# DDR3.net
KiCad netlist of a schematic drawn in Altium Designer
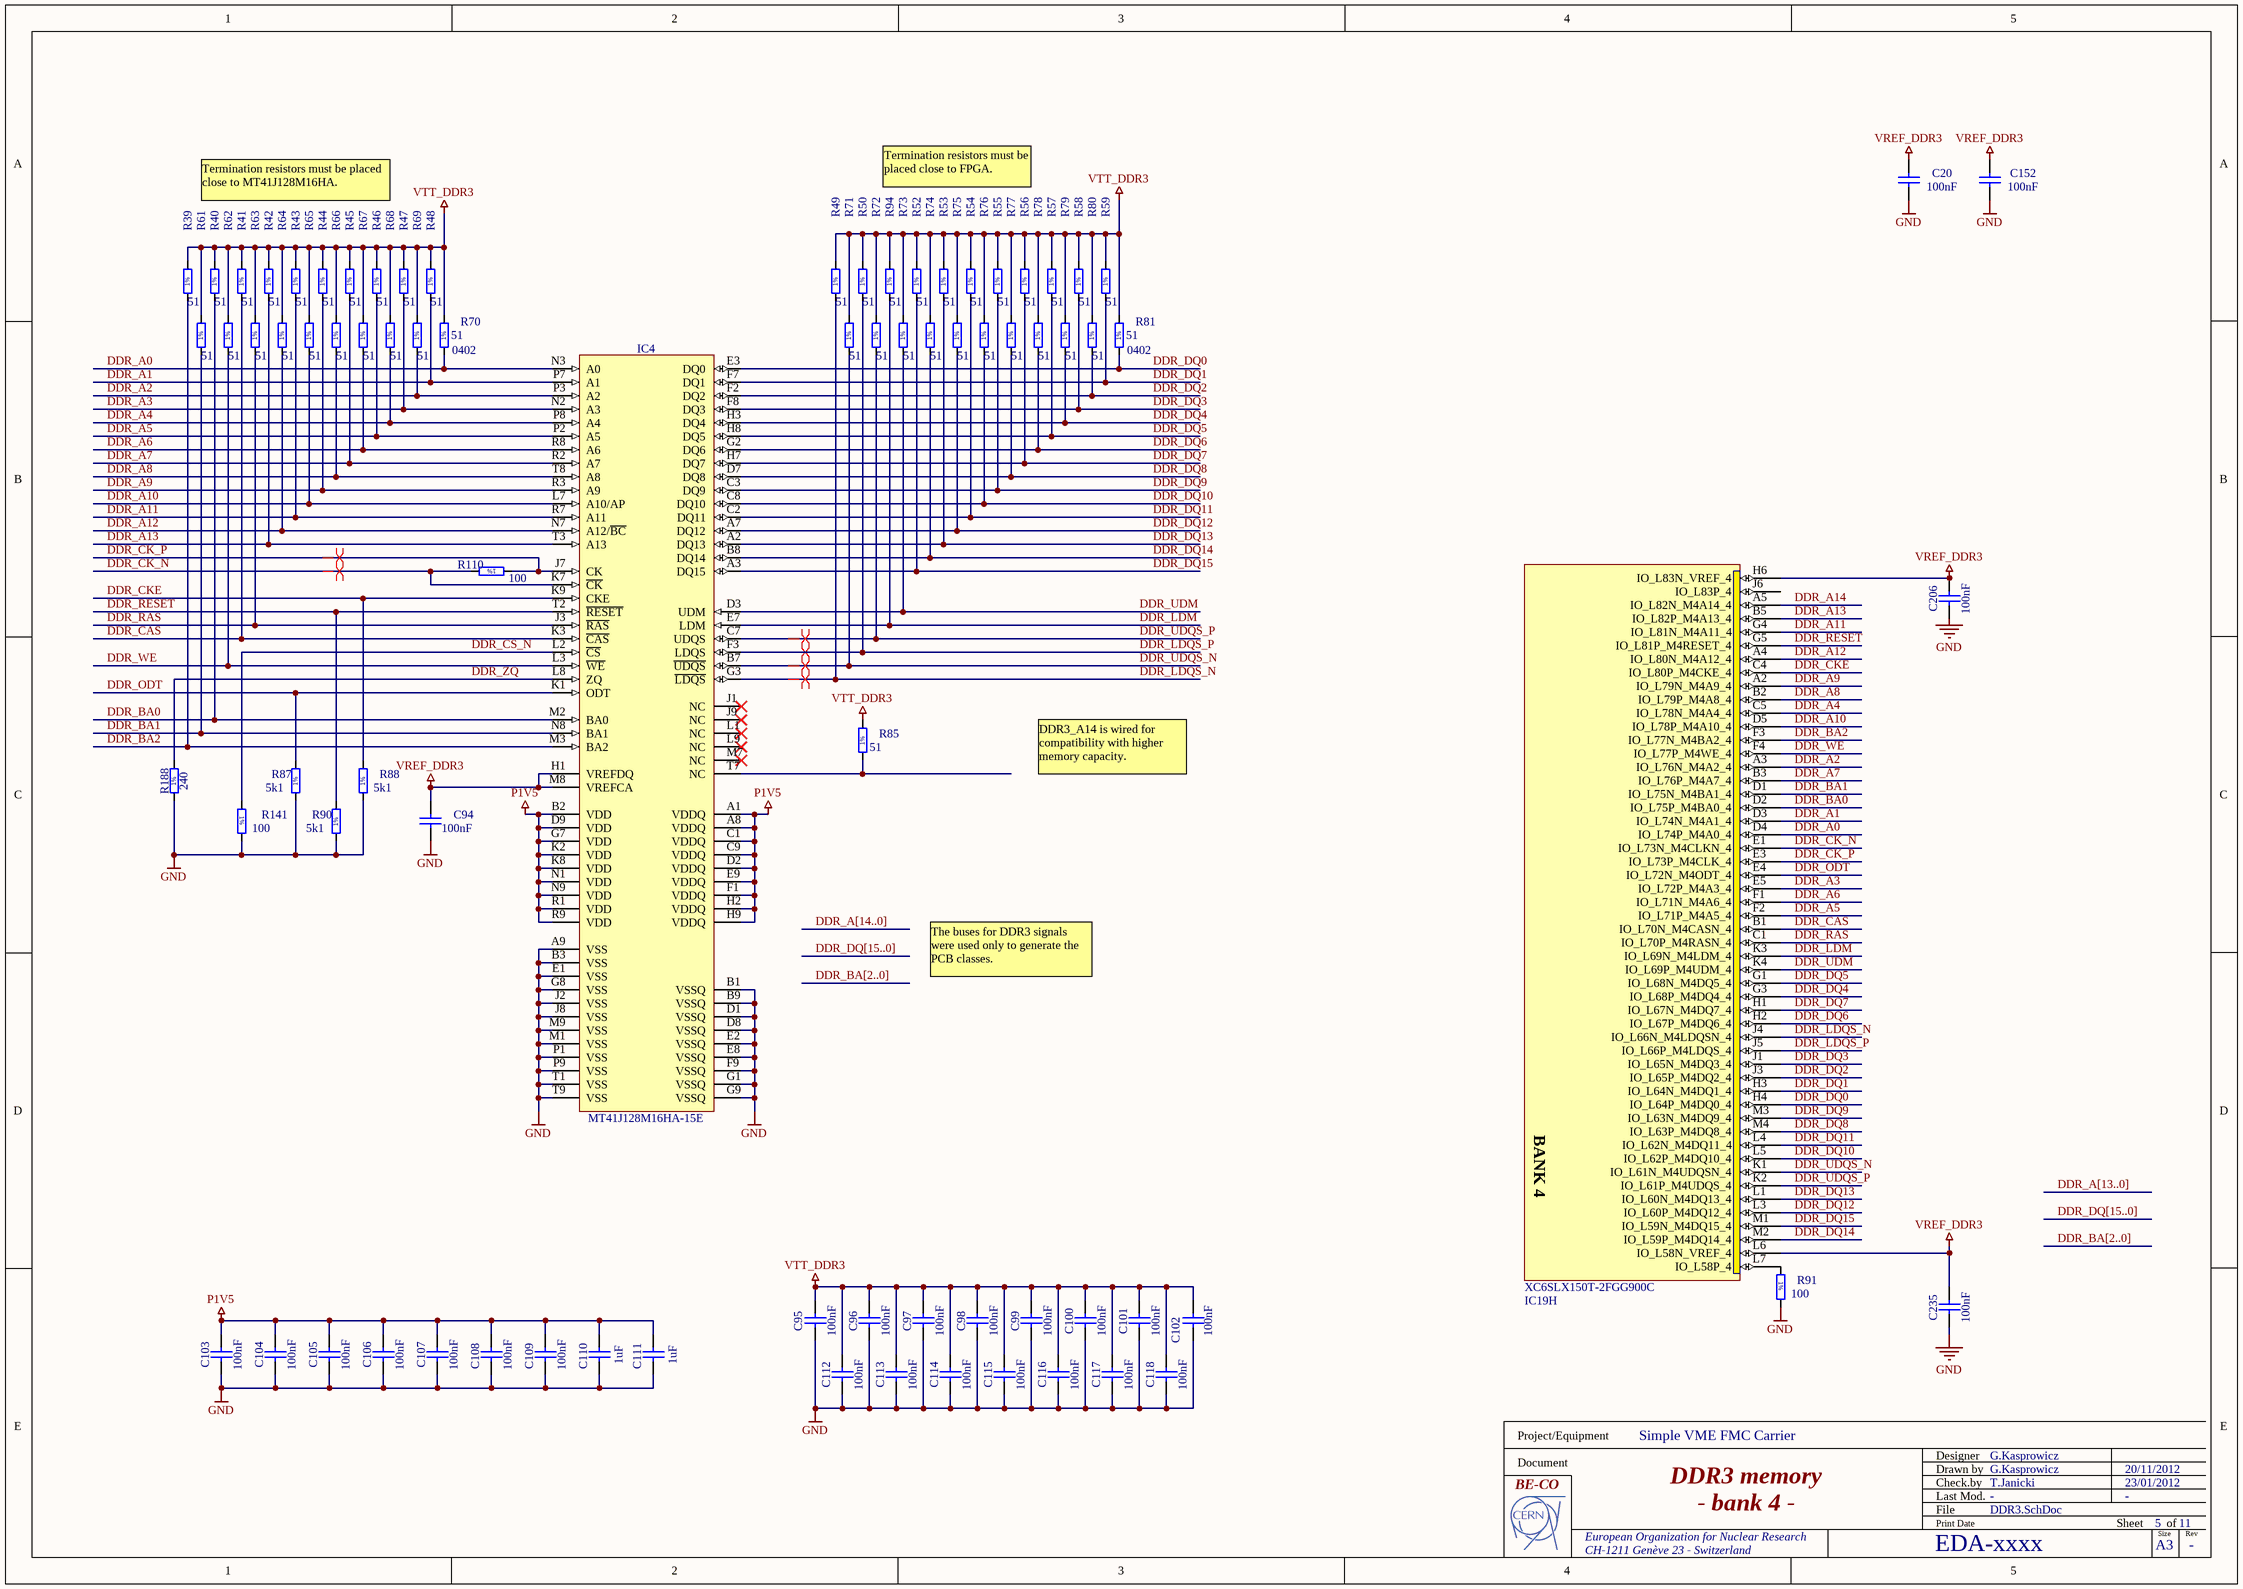
[diagram p0: DDR3.SchDoc]

(export (version "E")
  (design (tool "Eeschema 10.0.6"))
  (components
    (comp (ref "C20")
      (value "100nF")
      (footprint "CAPC1005X55N")
      (description "Non-polarised capacitor")
      (fields (field (name "PART NUMBER") "CC0402_100NF_16V_10%_X7R") (field (name "VOLTAGE") "16V"))
      (libsource (lib "Capacitors") (part "Capacitor - non polarized"))
    )
    (comp (ref "C94")
      (value "100nF")
      (footprint "CAPC1005X55N")
      (description "Non-polarised capacitor")
      (fields (field (name "PART NUMBER") "CC0402_100NF_16V_10%_X7R") (field (name "VOLTAGE") "16V"))
      (libsource (lib "Capacitors") (part "Capacitor - non polarized"))
    )
    (comp (ref "C95")
      (value "100nF")
      (footprint "CAPC1005X55N")
      (description "Non-polarised capacitor")
      (fields (field (name "PART NUMBER") "CC0402_100NF_16V_10%_X7R") (field (name "VOLTAGE") "16V"))
      (libsource (lib "Capacitors") (part "Capacitor - non polarized"))
    )
    (comp (ref "C96")
      (value "100nF")
      (footprint "CAPC1005X55N")
      (description "Non-polarised capacitor")
      (fields (field (name "PART NUMBER") "CC0402_100NF_16V_10%_X7R") (field (name "VOLTAGE") "16V"))
      (libsource (lib "Capacitors") (part "Capacitor - non polarized"))
    )
    (comp (ref "C97")
      (value "100nF")
      (footprint "CAPC1005X55N")
      (description "Non-polarised capacitor")
      (fields (field (name "PART NUMBER") "CC0402_100NF_16V_10%_X7R") (field (name "VOLTAGE") "16V"))
      (libsource (lib "Capacitors") (part "Capacitor - non polarized"))
    )
    (comp (ref "C98")
      (value "100nF")
      (footprint "CAPC1005X55N")
      (description "Non-polarised capacitor")
      (fields (field (name "PART NUMBER") "CC0402_100NF_16V_10%_X7R") (field (name "VOLTAGE") "16V"))
      (libsource (lib "Capacitors") (part "Capacitor - non polarized"))
    )
    (comp (ref "C99")
      (value "100nF")
      (footprint "CAPC1005X55N")
      (description "Non-polarised capacitor")
      (fields (field (name "PART NUMBER") "CC0402_100NF_16V_10%_X7R") (field (name "VOLTAGE") "16V"))
      (libsource (lib "Capacitors") (part "Capacitor - non polarized"))
    )
    (comp (ref "C100")
      (value "100nF")
      (footprint "CAPC1005X55N")
      (description "Non-polarised capacitor")
      (fields (field (name "PART NUMBER") "CC0402_100NF_16V_10%_X7R") (field (name "VOLTAGE") "16V"))
      (libsource (lib "Capacitors") (part "Capacitor - non polarized"))
    )
    (comp (ref "C101")
      (value "100nF")
      (footprint "CAPC1005X55N")
      (description "Non-polarised capacitor")
      (fields (field (name "PART NUMBER") "CC0402_100NF_16V_10%_X7R") (field (name "VOLTAGE") "16V"))
      (libsource (lib "Capacitors") (part "Capacitor - non polarized"))
    )
    (comp (ref "C102")
      (value "100nF")
      (footprint "CAPC1005X55N")
      (description "Non-polarised capacitor")
      (fields (field (name "PART NUMBER") "CC0402_100NF_16V_10%_X7R") (field (name "VOLTAGE") "16V"))
      (libsource (lib "Capacitors") (part "Capacitor - non polarized"))
    )
    (comp (ref "C103")
      (value "100nF")
      (footprint "CAPC1005X55N")
      (description "Non-polarised capacitor")
      (fields (field (name "PART NUMBER") "CC0402_100NF_16V_10%_X7R") (field (name "VOLTAGE") "16V"))
      (libsource (lib "Capacitors") (part "Capacitor - non polarized"))
    )
    (comp (ref "C104")
      (value "100nF")
      (footprint "CAPC1005X55N")
      (description "Non-polarised capacitor")
      (fields (field (name "PART NUMBER") "CC0402_100NF_16V_10%_X7R") (field (name "VOLTAGE") "16V"))
      (libsource (lib "Capacitors") (part "Capacitor - non polarized"))
    )
    (comp (ref "C105")
      (value "100nF")
      (footprint "CAPC1005X55N")
      (description "Non-polarised capacitor")
      (fields (field (name "PART NUMBER") "CC0402_100NF_16V_10%_X7R") (field (name "VOLTAGE") "16V"))
      (libsource (lib "Capacitors") (part "Capacitor - non polarized"))
    )
    (comp (ref "C106")
      (value "100nF")
      (footprint "CAPC1005X55N")
      (description "Non-polarised capacitor")
      (fields (field (name "PART NUMBER") "CC0402_100NF_16V_10%_X7R") (field (name "VOLTAGE") "16V"))
      (libsource (lib "Capacitors") (part "Capacitor - non polarized"))
    )
    (comp (ref "C107")
      (value "100nF")
      (footprint "CAPC1005X55N")
      (description "Non-polarised capacitor")
      (fields (field (name "PART NUMBER") "CC0402_100NF_16V_10%_X7R") (field (name "VOLTAGE") "16V"))
      (libsource (lib "Capacitors") (part "Capacitor - non polarized"))
    )
    (comp (ref "C108")
      (value "100nF")
      (footprint "CAPC1005X55N")
      (description "Non-polarised capacitor")
      (fields (field (name "PART NUMBER") "CC0402_100NF_16V_10%_X7R") (field (name "VOLTAGE") "16V"))
      (libsource (lib "Capacitors") (part "Capacitor - non polarized"))
    )
    (comp (ref "C109")
      (value "100nF")
      (footprint "CAPC1005X55N")
      (description "Non-polarised capacitor")
      (fields (field (name "PART NUMBER") "CC0402_100NF_16V_10%_X7R") (field (name "VOLTAGE") "16V"))
      (libsource (lib "Capacitors") (part "Capacitor - non polarized"))
    )
    (comp (ref "C110")
      (value "1uF")
      (footprint "CAPC1608X87N")
      (description "Non-polarised capacitor")
      (fields (field (name "PART NUMBER") "CC0603_1UF_16V_10%_X7R") (field (name "VOLTAGE") "16V"))
      (libsource (lib "Capacitors") (part "Capacitor - non polarized"))
    )
    (comp (ref "C111")
      (value "1uF")
      (footprint "CAPC1608X87N")
      (description "Non-polarised capacitor")
      (fields (field (name "PART NUMBER") "CC0603_1UF_16V_10%_X7R") (field (name "VOLTAGE") "16V"))
      (libsource (lib "Capacitors") (part "Capacitor - non polarized"))
    )
    (comp (ref "C112")
      (value "100nF")
      (footprint "CAPC1005X55N")
      (description "Non-polarised capacitor")
      (fields (field (name "PART NUMBER") "CC0402_100NF_16V_10%_X7R") (field (name "VOLTAGE") "16V"))
      (libsource (lib "Capacitors") (part "Capacitor - non polarized"))
    )
    (comp (ref "C113")
      (value "100nF")
      (footprint "CAPC1005X55N")
      (description "Non-polarised capacitor")
      (fields (field (name "PART NUMBER") "CC0402_100NF_16V_10%_X7R") (field (name "VOLTAGE") "16V"))
      (libsource (lib "Capacitors") (part "Capacitor - non polarized"))
    )
    (comp (ref "C114")
      (value "100nF")
      (footprint "CAPC1005X55N")
      (description "Non-polarised capacitor")
      (fields (field (name "PART NUMBER") "CC0402_100NF_16V_10%_X7R") (field (name "VOLTAGE") "16V"))
      (libsource (lib "Capacitors") (part "Capacitor - non polarized"))
    )
    (comp (ref "C115")
      (value "100nF")
      (footprint "CAPC1005X55N")
      (description "Non-polarised capacitor")
      (fields (field (name "PART NUMBER") "CC0402_100NF_16V_10%_X7R") (field (name "VOLTAGE") "16V"))
      (libsource (lib "Capacitors") (part "Capacitor - non polarized"))
    )
    (comp (ref "C116")
      (value "100nF")
      (footprint "CAPC1005X55N")
      (description "Non-polarised capacitor")
      (fields (field (name "PART NUMBER") "CC0402_100NF_16V_10%_X7R") (field (name "VOLTAGE") "16V"))
      (libsource (lib "Capacitors") (part "Capacitor - non polarized"))
    )
    (comp (ref "C117")
      (value "100nF")
      (footprint "CAPC1005X55N")
      (description "Non-polarised capacitor")
      (fields (field (name "PART NUMBER") "CC0402_100NF_16V_10%_X7R") (field (name "VOLTAGE") "16V"))
      (libsource (lib "Capacitors") (part "Capacitor - non polarized"))
    )
    (comp (ref "C118")
      (value "100nF")
      (footprint "CAPC1005X55N")
      (description "Non-polarised capacitor")
      (fields (field (name "PART NUMBER") "CC0402_100NF_16V_10%_X7R") (field (name "VOLTAGE") "16V"))
      (libsource (lib "Capacitors") (part "Capacitor - non polarized"))
    )
    (comp (ref "C152")
      (value "100nF")
      (footprint "CAPC1005X55N")
      (description "Non-polarised capacitor")
      (fields (field (name "PART NUMBER") "CC0402_100NF_16V_10%_X7R") (field (name "VOLTAGE") "16V"))
      (libsource (lib "Capacitors") (part "Capacitor - non polarized"))
    )
    (comp (ref "C206")
      (value "100nF")
      (footprint "CAPC1005X55N")
      (description "Non-polarised capacitor")
      (fields (field (name "PART NUMBER") "CC0402_100NF_16V_10%_X7R") (field (name "VOLTAGE") "16V"))
      (libsource (lib "Capacitors") (part "Capacitor - non polarized"))
    )
    (comp (ref "C235")
      (value "100nF")
      (footprint "CAPC1005X55N")
      (description "Non-polarised capacitor")
      (fields (field (name "PART NUMBER") "CC0402_100NF_16V_10%_X7R") (field (name "VOLTAGE") "16V"))
      (libsource (lib "Capacitors") (part "Capacitor - non polarized"))
    )
    (comp (ref "IC4")
      (value "MT41J128M16HA-15E")
      (footprint "BGA96C80P9X16_900X1400X120")
      (description "16 Meg x 16 x 8 Banks DDR3 SDRAM")
      (fields (field (name "MANUFACTURER") "MICRON TECHNOLOGY"))
      (libsource (lib "ICs And Semiconductors") (part "MT41J128M16HA"))
    )
    (comp (ref "IC19")
      (value "XC6SLX150T-2FGG900C")
      (footprint "BGA900C100P30X30_3100X3100X260")
      (description "SPARTAN-6, FPGA, 900-Ball BGA, Commercial Grade, Pb-Free")
      (fields (field (name "MANUFACTURER") "XILINX"))
      (libsource (lib "ICs And Semiconductors") (part "XC6SLX150T-2FGG900C"))
    )
    (comp (ref "R39")
      (value "51")
      (footprint "RESC1005X40N")
      (description "Resistor - 1%")
      (fields (field (name "PART NUMBER") "R0402_51R_1%_0.0625W_100PPM") (field (name "POWER") "0.0625W"))
      (libsource (lib "Resistors") (part "Resistor - 1%"))
    )
    (comp (ref "R40")
      (value "51")
      (footprint "RESC1005X40N")
      (description "Resistor - 1%")
      (fields (field (name "PART NUMBER") "R0402_51R_1%_0.0625W_100PPM") (field (name "POWER") "0.0625W"))
      (libsource (lib "Resistors") (part "Resistor - 1%"))
    )
    (comp (ref "R41")
      (value "51")
      (footprint "RESC1005X40N")
      (description "Resistor - 1%")
      (fields (field (name "PART NUMBER") "R0402_51R_1%_0.0625W_100PPM") (field (name "POWER") "0.0625W"))
      (libsource (lib "Resistors") (part "Resistor - 1%"))
    )
    (comp (ref "R42")
      (value "51")
      (footprint "RESC1005X40N")
      (description "Resistor - 1%")
      (fields (field (name "PART NUMBER") "R0402_51R_1%_0.0625W_100PPM") (field (name "POWER") "0.0625W"))
      (libsource (lib "Resistors") (part "Resistor - 1%"))
    )
    (comp (ref "R43")
      (value "51")
      (footprint "RESC1005X40N")
      (description "Resistor - 1%")
      (fields (field (name "PART NUMBER") "R0402_51R_1%_0.0625W_100PPM") (field (name "POWER") "0.0625W"))
      (libsource (lib "Resistors") (part "Resistor - 1%"))
    )
    (comp (ref "R44")
      (value "51")
      (footprint "RESC1005X40N")
      (description "Resistor - 1%")
      (fields (field (name "PART NUMBER") "R0402_51R_1%_0.0625W_100PPM") (field (name "POWER") "0.0625W"))
      (libsource (lib "Resistors") (part "Resistor - 1%"))
    )
    (comp (ref "R45")
      (value "51")
      (footprint "RESC1005X40N")
      (description "Resistor - 1%")
      (fields (field (name "PART NUMBER") "R0402_51R_1%_0.0625W_100PPM") (field (name "POWER") "0.0625W"))
      (libsource (lib "Resistors") (part "Resistor - 1%"))
    )
    (comp (ref "R46")
      (value "51")
      (footprint "RESC1005X40N")
      (description "Resistor - 1%")
      (fields (field (name "PART NUMBER") "R0402_51R_1%_0.0625W_100PPM") (field (name "POWER") "0.0625W"))
      (libsource (lib "Resistors") (part "Resistor - 1%"))
    )
    (comp (ref "R47")
      (value "51")
      (footprint "RESC1005X40N")
      (description "Resistor - 1%")
      (fields (field (name "PART NUMBER") "R0402_51R_1%_0.0625W_100PPM") (field (name "POWER") "0.0625W"))
      (libsource (lib "Resistors") (part "Resistor - 1%"))
    )
    (comp (ref "R48")
      (value "51")
      (footprint "RESC1005X40N")
      (description "Resistor - 1%")
      (fields (field (name "PART NUMBER") "R0402_51R_1%_0.0625W_100PPM") (field (name "POWER") "0.0625W"))
      (libsource (lib "Resistors") (part "Resistor - 1%"))
    )
    (comp (ref "R49")
      (value "51")
      (footprint "RESC1005X40N")
      (description "Resistor - 1%")
      (fields (field (name "PART NUMBER") "R0402_51R_1%_0.0625W_100PPM") (field (name "POWER") "0.0625W"))
      (libsource (lib "Resistors") (part "Resistor - 1%"))
    )
    (comp (ref "R50")
      (value "51")
      (footprint "RESC1005X40N")
      (description "Resistor - 1%")
      (fields (field (name "PART NUMBER") "R0402_51R_1%_0.0625W_100PPM") (field (name "POWER") "0.0625W"))
      (libsource (lib "Resistors") (part "Resistor - 1%"))
    )
    (comp (ref "R52")
      (value "51")
      (footprint "RESC1005X40N")
      (description "Resistor - 1%")
      (fields (field (name "PART NUMBER") "R0402_51R_1%_0.0625W_100PPM") (field (name "POWER") "0.0625W"))
      (libsource (lib "Resistors") (part "Resistor - 1%"))
    )
    (comp (ref "R53")
      (value "51")
      (footprint "RESC1005X40N")
      (description "Resistor - 1%")
      (fields (field (name "PART NUMBER") "R0402_51R_1%_0.0625W_100PPM") (field (name "POWER") "0.0625W"))
      (libsource (lib "Resistors") (part "Resistor - 1%"))
    )
    (comp (ref "R54")
      (value "51")
      (footprint "RESC1005X40N")
      (description "Resistor - 1%")
      (fields (field (name "PART NUMBER") "R0402_51R_1%_0.0625W_100PPM") (field (name "POWER") "0.0625W"))
      (libsource (lib "Resistors") (part "Resistor - 1%"))
    )
    (comp (ref "R55")
      (value "51")
      (footprint "RESC1005X40N")
      (description "Resistor - 1%")
      (fields (field (name "PART NUMBER") "R0402_51R_1%_0.0625W_100PPM") (field (name "POWER") "0.0625W"))
      (libsource (lib "Resistors") (part "Resistor - 1%"))
    )
    (comp (ref "R56")
      (value "51")
      (footprint "RESC1005X40N")
      (description "Resistor - 1%")
      (fields (field (name "PART NUMBER") "R0402_51R_1%_0.0625W_100PPM") (field (name "POWER") "0.0625W"))
      (libsource (lib "Resistors") (part "Resistor - 1%"))
    )
    (comp (ref "R57")
      (value "51")
      (footprint "RESC1005X40N")
      (description "Resistor - 1%")
      (fields (field (name "PART NUMBER") "R0402_51R_1%_0.0625W_100PPM") (field (name "POWER") "0.0625W"))
      (libsource (lib "Resistors") (part "Resistor - 1%"))
    )
    (comp (ref "R58")
      (value "51")
      (footprint "RESC1005X40N")
      (description "Resistor - 1%")
      (fields (field (name "PART NUMBER") "R0402_51R_1%_0.0625W_100PPM") (field (name "POWER") "0.0625W"))
      (libsource (lib "Resistors") (part "Resistor - 1%"))
    )
    (comp (ref "R59")
      (value "51")
      (footprint "RESC1005X40N")
      (description "Resistor - 1%")
      (fields (field (name "PART NUMBER") "R0402_51R_1%_0.0625W_100PPM") (field (name "POWER") "0.0625W"))
      (libsource (lib "Resistors") (part "Resistor - 1%"))
    )
    (comp (ref "R61")
      (value "51")
      (footprint "RESC1005X40N")
      (description "Resistor - 1%")
      (fields (field (name "PART NUMBER") "R0402_51R_1%_0.0625W_100PPM") (field (name "POWER") "0.0625W"))
      (libsource (lib "Resistors") (part "Resistor - 1%"))
    )
    (comp (ref "R62")
      (value "51")
      (footprint "RESC1005X40N")
      (description "Resistor - 1%")
      (fields (field (name "PART NUMBER") "R0402_51R_1%_0.0625W_100PPM") (field (name "POWER") "0.0625W"))
      (libsource (lib "Resistors") (part "Resistor - 1%"))
    )
    (comp (ref "R63")
      (value "51")
      (footprint "RESC1005X40N")
      (description "Resistor - 1%")
      (fields (field (name "PART NUMBER") "R0402_51R_1%_0.0625W_100PPM") (field (name "POWER") "0.0625W"))
      (libsource (lib "Resistors") (part "Resistor - 1%"))
    )
    (comp (ref "R64")
      (value "51")
      (footprint "RESC1005X40N")
      (description "Resistor - 1%")
      (fields (field (name "PART NUMBER") "R0402_51R_1%_0.0625W_100PPM") (field (name "POWER") "0.0625W"))
      (libsource (lib "Resistors") (part "Resistor - 1%"))
    )
    (comp (ref "R65")
      (value "51")
      (footprint "RESC1005X40N")
      (description "Resistor - 1%")
      (fields (field (name "PART NUMBER") "R0402_51R_1%_0.0625W_100PPM") (field (name "POWER") "0.0625W"))
      (libsource (lib "Resistors") (part "Resistor - 1%"))
    )
    (comp (ref "R66")
      (value "51")
      (footprint "RESC1005X40N")
      (description "Resistor - 1%")
      (fields (field (name "PART NUMBER") "R0402_51R_1%_0.0625W_100PPM") (field (name "POWER") "0.0625W"))
      (libsource (lib "Resistors") (part "Resistor - 1%"))
    )
    (comp (ref "R67")
      (value "51")
      (footprint "RESC1005X40N")
      (description "Resistor - 1%")
      (fields (field (name "PART NUMBER") "R0402_51R_1%_0.0625W_100PPM") (field (name "POWER") "0.0625W"))
      (libsource (lib "Resistors") (part "Resistor - 1%"))
    )
    (comp (ref "R68")
      (value "51")
      (footprint "RESC1005X40N")
      (description "Resistor - 1%")
      (fields (field (name "PART NUMBER") "R0402_51R_1%_0.0625W_100PPM") (field (name "POWER") "0.0625W"))
      (libsource (lib "Resistors") (part "Resistor - 1%"))
    )
    (comp (ref "R69")
      (value "51")
      (footprint "RESC1005X40N")
      (description "Resistor - 1%")
      (fields (field (name "PART NUMBER") "R0402_51R_1%_0.0625W_100PPM") (field (name "POWER") "0.0625W"))
      (libsource (lib "Resistors") (part "Resistor - 1%"))
    )
    (comp (ref "R70")
      (value "51")
      (footprint "RESC1005X40N")
      (description "Resistor - 1%")
      (fields
        (field (name "PART NUMBER") "R0402_51R_1%_0.0625W_100PPM")
        (field (name "POWER") "0.0625W")
        (field (name "CASE") "0402")
      )
      (libsource (lib "Resistors") (part "Resistor - 1%"))
    )
    (comp (ref "R71")
      (value "51")
      (footprint "RESC1005X40N")
      (description "Resistor - 1%")
      (fields (field (name "PART NUMBER") "R0402_51R_1%_0.0625W_100PPM") (field (name "POWER") "0.0625W"))
      (libsource (lib "Resistors") (part "Resistor - 1%"))
    )
    (comp (ref "R72")
      (value "51")
      (footprint "RESC1005X40N")
      (description "Resistor - 1%")
      (fields (field (name "PART NUMBER") "R0402_51R_1%_0.0625W_100PPM") (field (name "POWER") "0.0625W"))
      (libsource (lib "Resistors") (part "Resistor - 1%"))
    )
    (comp (ref "R73")
      (value "51")
      (footprint "RESC1005X40N")
      (description "Resistor - 1%")
      (fields (field (name "PART NUMBER") "R0402_51R_1%_0.0625W_100PPM") (field (name "POWER") "0.0625W"))
      (libsource (lib "Resistors") (part "Resistor - 1%"))
    )
    (comp (ref "R74")
      (value "51")
      (footprint "RESC1005X40N")
      (description "Resistor - 1%")
      (fields (field (name "PART NUMBER") "R0402_51R_1%_0.0625W_100PPM") (field (name "POWER") "0.0625W"))
      (libsource (lib "Resistors") (part "Resistor - 1%"))
    )
    (comp (ref "R75")
      (value "51")
      (footprint "RESC1005X40N")
      (description "Resistor - 1%")
      (fields (field (name "PART NUMBER") "R0402_51R_1%_0.0625W_100PPM") (field (name "POWER") "0.0625W"))
      (libsource (lib "Resistors") (part "Resistor - 1%"))
    )
    (comp (ref "R76")
      (value "51")
      (footprint "RESC1005X40N")
      (description "Resistor - 1%")
      (fields (field (name "PART NUMBER") "R0402_51R_1%_0.0625W_100PPM") (field (name "POWER") "0.0625W"))
      (libsource (lib "Resistors") (part "Resistor - 1%"))
    )
    (comp (ref "R77")
      (value "51")
      (footprint "RESC1005X40N")
      (description "Resistor - 1%")
      (fields (field (name "PART NUMBER") "R0402_51R_1%_0.0625W_100PPM") (field (name "POWER") "0.0625W"))
      (libsource (lib "Resistors") (part "Resistor - 1%"))
    )
    (comp (ref "R78")
      (value "51")
      (footprint "RESC1005X40N")
      (description "Resistor - 1%")
      (fields (field (name "PART NUMBER") "R0402_51R_1%_0.0625W_100PPM") (field (name "POWER") "0.0625W"))
      (libsource (lib "Resistors") (part "Resistor - 1%"))
    )
    (comp (ref "R79")
      (value "51")
      (footprint "RESC1005X40N")
      (description "Resistor - 1%")
      (fields (field (name "PART NUMBER") "R0402_51R_1%_0.0625W_100PPM") (field (name "POWER") "0.0625W"))
      (libsource (lib "Resistors") (part "Resistor - 1%"))
    )
    (comp (ref "R80")
      (value "51")
      (footprint "RESC1005X40N")
      (description "Resistor - 1%")
      (fields (field (name "PART NUMBER") "R0402_51R_1%_0.0625W_100PPM") (field (name "POWER") "0.0625W"))
      (libsource (lib "Resistors") (part "Resistor - 1%"))
    )
    (comp (ref "R81")
      (value "51")
      (footprint "RESC1005X40N")
      (description "Resistor - 1%")
      (fields
        (field (name "PART NUMBER") "R0402_51R_1%_0.0625W_100PPM")
        (field (name "POWER") "0.0625W")
        (field (name "CASE") "0402")
      )
      (libsource (lib "Resistors") (part "Resistor - 1%"))
    )
    (comp (ref "R85")
      (value "51")
      (footprint "RESC1005X40N")
      (description "Resistor - 1%")
      (fields (field (name "PART NUMBER") "R0402_51R_1%_0.0625W_100PPM") (field (name "POWER") "0.0625W"))
      (libsource (lib "Resistors") (part "Resistor - 1%"))
    )
    (comp (ref "R87")
      (value "5k1")
      (footprint "RESC1608X55N")
      (description "Resistor - 1%")
      (fields (field (name "PART NUMBER") "R0603_5K1_1%_0.1W_100PPM") (field (name "POWER") "0.1W"))
      (libsource (lib "Resistors") (part "Resistor - 1%"))
    )
    (comp (ref "R88")
      (value "5k1")
      (footprint "RESC1608X55N")
      (description "Resistor - 1%")
      (fields (field (name "PART NUMBER") "R0603_5K1_1%_0.1W_100PPM") (field (name "POWER") "0.1W"))
      (libsource (lib "Resistors") (part "Resistor - 1%"))
    )
    (comp (ref "R90")
      (value "5k1")
      (footprint "RESC1608X55N")
      (description "Resistor - 1%")
      (fields (field (name "PART NUMBER") "R0603_5K1_1%_0.1W_100PPM") (field (name "POWER") "0.1W"))
      (libsource (lib "Resistors") (part "Resistor - 1%"))
    )
    (comp (ref "R91")
      (value "100")
      (footprint "RESC1608X55N")
      (description "Resistor - 1%")
      (fields (field (name "PART NUMBER") "R0603_100R_1%_0.1W_100PPM") (field (name "POWER") "0.1W"))
      (libsource (lib "Resistors") (part "Resistor - 1%"))
    )
    (comp (ref "R94")
      (value "51")
      (footprint "RESC1005X40N")
      (description "Resistor - 1%")
      (fields (field (name "PART NUMBER") "R0402_51R_1%_0.0625W_100PPM") (field (name "POWER") "0.0625W"))
      (libsource (lib "Resistors") (part "Resistor - 1%"))
    )
    (comp (ref "R110")
      (value "100")
      (footprint "RESC1608X55N")
      (description "Resistor - 1%")
      (fields (field (name "PART NUMBER") "R0603_100R_1%_0.1W_100PPM") (field (name "POWER") "0.1W"))
      (libsource (lib "Resistors") (part "Resistor - 1%"))
    )
    (comp (ref "R141")
      (value "100")
      (footprint "RESC1608X55N")
      (description "Resistor - 1%")
      (fields (field (name "PART NUMBER") "R0603_100R_1%_0.1W_100PPM") (field (name "POWER") "0.1W"))
      (libsource (lib "Resistors") (part "Resistor - 1%"))
    )
    (comp (ref "R188")
      (value "240")
      (footprint "RESC1608X55N")
      (description "Resistor - 1%")
      (fields (field (name "PART NUMBER") "R0603_240R_1%_0.1W_100PPM") (field (name "POWER") "0.1W"))
      (libsource (lib "Resistors") (part "Resistor - 1%"))
    )
  )
  (nets
    (net (code "1") (name "/DDR_A0") (class "Default")
      (node (ref "IC19") (pin "D4") (pinfunction "IO_L74P_M4A0_4_D4") (pintype "bidirectional"))
      (node (ref "IC4") (pin "N3") (pinfunction "A0_N3") (pintype "input"))
      (node (ref "R70") (pin "1") (pinfunction "1_1") (pintype "passive"))
    )
    (net (code "2") (name "/DDR_A1") (class "Default")
      (node (ref "IC19") (pin "D3") (pinfunction "IO_L74N_M4A1_4_D3") (pintype "bidirectional"))
      (node (ref "IC4") (pin "P7") (pinfunction "A1_P7") (pintype "input"))
      (node (ref "R48") (pin "1") (pinfunction "1_1") (pintype "passive"))
    )
    (net (code "3") (name "/DDR_A2") (class "Default")
      (node (ref "IC19") (pin "A3") (pinfunction "IO_L76N_M4A2_4_A3") (pintype "bidirectional"))
      (node (ref "IC4") (pin "P3") (pinfunction "A2_P3") (pintype "input"))
      (node (ref "R69") (pin "1") (pinfunction "1_1") (pintype "passive"))
    )
    (net (code "4") (name "/DDR_A3") (class "Default")
      (node (ref "IC19") (pin "E5") (pinfunction "IO_L72P_M4A3_4_E5") (pintype "bidirectional"))
      (node (ref "IC4") (pin "N2") (pinfunction "A3_N2") (pintype "input"))
      (node (ref "R47") (pin "1") (pinfunction "1_1") (pintype "passive"))
    )
    (net (code "5") (name "/DDR_A4") (class "Default")
      (node (ref "IC19") (pin "C5") (pinfunction "IO_L78N_M4A4_4_C5") (pintype "bidirectional"))
      (node (ref "IC4") (pin "P8") (pinfunction "A4_P8") (pintype "input"))
      (node (ref "R68") (pin "1") (pinfunction "1_1") (pintype "passive"))
    )
    (net (code "6") (name "/DDR_A5") (class "Default")
      (node (ref "IC19") (pin "F2") (pinfunction "IO_L71P_M4A5_4_F2") (pintype "bidirectional"))
      (node (ref "IC4") (pin "P2") (pinfunction "A5_P2") (pintype "input"))
      (node (ref "R46") (pin "1") (pinfunction "1_1") (pintype "passive"))
    )
    (net (code "7") (name "/DDR_A6") (class "Default")
      (node (ref "IC19") (pin "F1") (pinfunction "IO_L71N_M4A6_4_F1") (pintype "bidirectional"))
      (node (ref "IC4") (pin "R8") (pinfunction "A6_R8") (pintype "input"))
      (node (ref "R67") (pin "1") (pinfunction "1_1") (pintype "passive"))
    )
    (net (code "8") (name "/DDR_A7") (class "Default")
      (node (ref "IC19") (pin "B3") (pinfunction "IO_L76P_M4A7_4_B3") (pintype "bidirectional"))
      (node (ref "IC4") (pin "R2") (pinfunction "A7_R2") (pintype "input"))
      (node (ref "R45") (pin "1") (pinfunction "1_1") (pintype "passive"))
    )
    (net (code "9") (name "/DDR_A8") (class "Default")
      (node (ref "IC19") (pin "B2") (pinfunction "IO_L79P_M4A8_4_B2") (pintype "bidirectional"))
      (node (ref "IC4") (pin "T8") (pinfunction "A8_T8") (pintype "input"))
      (node (ref "R66") (pin "1") (pinfunction "1_1") (pintype "passive"))
    )
    (net (code "10") (name "/DDR_A9") (class "Default")
      (node (ref "IC19") (pin "A2") (pinfunction "IO_L79N_M4A9_4_A2") (pintype "bidirectional"))
      (node (ref "IC4") (pin "R3") (pinfunction "A9_R3") (pintype "input"))
      (node (ref "R44") (pin "1") (pinfunction "1_1") (pintype "passive"))
    )
    (net (code "11") (name "/DDR_A10") (class "Default")
      (node (ref "IC19") (pin "D5") (pinfunction "IO_L78P_M4A10_4_D5") (pintype "bidirectional"))
      (node (ref "IC4") (pin "L7") (pinfunction "A10/AP_L7") (pintype "input"))
      (node (ref "R65") (pin "1") (pinfunction "1_1") (pintype "passive"))
    )
    (net (code "12") (name "/DDR_A11") (class "Default")
      (node (ref "IC19") (pin "G4") (pinfunction "IO_L81N_M4A11_4_G4") (pintype "bidirectional"))
      (node (ref "IC4") (pin "R7") (pinfunction "A11_R7") (pintype "input"))
      (node (ref "R43") (pin "1") (pinfunction "1_1") (pintype "passive"))
    )
    (net (code "13") (name "/DDR_A12") (class "Default")
      (node (ref "IC19") (pin "A4") (pinfunction "IO_L80N_M4A12_4_A4") (pintype "bidirectional"))
      (node (ref "IC4") (pin "N7") (pinfunction "A12/~{BC}_N7") (pintype "input"))
      (node (ref "R64") (pin "1") (pinfunction "1_1") (pintype "passive"))
    )
    (net (code "14") (name "/DDR_A13") (class "Default")
      (node (ref "IC19") (pin "B5") (pinfunction "IO_L82P_M4A13_4_B5") (pintype "bidirectional"))
      (node (ref "IC4") (pin "T3") (pinfunction "A13_T3") (pintype "input"))
      (node (ref "R42") (pin "1") (pinfunction "1_1") (pintype "passive"))
    )
    (net (code "15") (name "/DDR_A14") (class "Default")
      (node (ref "IC19") (pin "A5") (pinfunction "IO_L82N_M4A14_4_A5") (pintype "bidirectional"))
    )
    (net (code "18") (name "/DDR_BA0") (class "Default")
      (node (ref "IC19") (pin "D2") (pinfunction "IO_L75P_M4BA0_4_D2") (pintype "bidirectional"))
      (node (ref "IC4") (pin "M2") (pinfunction "BA0_M2") (pintype "input"))
      (node (ref "R40") (pin "1") (pinfunction "1_1") (pintype "passive"))
    )
    (net (code "19") (name "/DDR_BA1") (class "Default")
      (node (ref "IC19") (pin "D1") (pinfunction "IO_L75N_M4BA1_4_D1") (pintype "bidirectional"))
      (node (ref "IC4") (pin "N8") (pinfunction "BA1_N8") (pintype "input"))
      (node (ref "R61") (pin "1") (pinfunction "1_1") (pintype "passive"))
    )
    (net (code "20") (name "/DDR_BA2") (class "Default")
      (node (ref "IC19") (pin "F3") (pinfunction "IO_L77N_M4BA2_4_F3") (pintype "bidirectional"))
      (node (ref "IC4") (pin "M3") (pinfunction "BA2_M3") (pintype "input"))
      (node (ref "R39") (pin "1") (pinfunction "1_1") (pintype "passive"))
    )
    (net (code "22") (name "/DDR_CAS") (class "Default")
      (node (ref "IC19") (pin "B1") (pinfunction "IO_L70N_M4CASN_4_B1") (pintype "bidirectional"))
      (node (ref "IC4") (pin "K3") (pinfunction "CAS_K3") (pintype "input"))
      (node (ref "R41") (pin "1") (pinfunction "1_1") (pintype "passive"))
    )
    (net (code "23") (name "/DDR_CKE") (class "Default")
      (node (ref "IC19") (pin "C4") (pinfunction "IO_L80P_M4CKE_4_C4") (pintype "bidirectional"))
      (node (ref "IC4") (pin "K9") (pinfunction "CKE_K9") (pintype "input"))
      (node (ref "R88") (pin "2") (pinfunction "2_2") (pintype "passive"))
    )
    (net (code "24") (name "/DDR_CK_N") (class "Default")
      (node (ref "IC19") (pin "E1") (pinfunction "IO_L73N_M4CLKN_4_E1") (pintype "bidirectional"))
      (node (ref "IC4") (pin "K7") (pinfunction "CK_K7") (pintype "input"))
      (node (ref "R110") (pin "2") (pinfunction "2_2") (pintype "passive"))
    )
    (net (code "25") (name "/DDR_CK_P") (class "Default")
      (node (ref "IC19") (pin "E3") (pinfunction "IO_L73P_M4CLK_4_E3") (pintype "bidirectional"))
      (node (ref "IC4") (pin "J7") (pinfunction "CK_J7") (pintype "input"))
      (node (ref "R110") (pin "1") (pinfunction "1_1") (pintype "passive"))
    )
    (net (code "26") (name "/DDR_CS_N") (class "Default")
      (node (ref "IC4") (pin "L2") (pinfunction "CS_L2") (pintype "input"))
      (node (ref "R141") (pin "1") (pinfunction "1_1") (pintype "passive"))
    )
    (net (code "27") (name "/DDR_DQ0") (class "Default")
      (node (ref "IC19") (pin "H4") (pinfunction "IO_L64P_M4DQ0_4_H4") (pintype "bidirectional"))
      (node (ref "IC4") (pin "E3") (pinfunction "DQ0_E3") (pintype "bidirectional"))
      (node (ref "R81") (pin "1") (pinfunction "1_1") (pintype "passive"))
    )
    (net (code "28") (name "/DDR_DQ1") (class "Default")
      (node (ref "IC19") (pin "H3") (pinfunction "IO_L64N_M4DQ1_4_H3") (pintype "bidirectional"))
      (node (ref "IC4") (pin "F7") (pinfunction "DQ1_F7") (pintype "bidirectional"))
      (node (ref "R59") (pin "1") (pinfunction "1_1") (pintype "passive"))
    )
    (net (code "29") (name "/DDR_DQ2") (class "Default")
      (node (ref "IC19") (pin "J3") (pinfunction "IO_L65P_M4DQ2_4_J3") (pintype "bidirectional"))
      (node (ref "IC4") (pin "F2") (pinfunction "DQ2_F2") (pintype "bidirectional"))
      (node (ref "R80") (pin "1") (pinfunction "1_1") (pintype "passive"))
    )
    (net (code "30") (name "/DDR_DQ3") (class "Default")
      (node (ref "IC19") (pin "J1") (pinfunction "IO_L65N_M4DQ3_4_J1") (pintype "bidirectional"))
      (node (ref "IC4") (pin "F8") (pinfunction "DQ3_F8") (pintype "bidirectional"))
      (node (ref "R58") (pin "1") (pinfunction "1_1") (pintype "passive"))
    )
    (net (code "31") (name "/DDR_DQ4") (class "Default")
      (node (ref "IC19") (pin "G3") (pinfunction "IO_L68P_M4DQ4_4_G3") (pintype "bidirectional"))
      (node (ref "IC4") (pin "H3") (pinfunction "DQ4_H3") (pintype "bidirectional"))
      (node (ref "R79") (pin "1") (pinfunction "1_1") (pintype "passive"))
    )
    (net (code "32") (name "/DDR_DQ5") (class "Default")
      (node (ref "IC19") (pin "G1") (pinfunction "IO_L68N_M4DQ5_4_G1") (pintype "bidirectional"))
      (node (ref "IC4") (pin "H8") (pinfunction "DQ5_H8") (pintype "bidirectional"))
      (node (ref "R57") (pin "1") (pinfunction "1_1") (pintype "passive"))
    )
    (net (code "33") (name "/DDR_DQ6") (class "Default")
      (node (ref "IC19") (pin "H2") (pinfunction "IO_L67P_M4DQ6_4_H2") (pintype "bidirectional"))
      (node (ref "IC4") (pin "G2") (pinfunction "DQ6_G2") (pintype "bidirectional"))
      (node (ref "R78") (pin "1") (pinfunction "1_1") (pintype "passive"))
    )
    (net (code "34") (name "/DDR_DQ7") (class "Default")
      (node (ref "IC19") (pin "H1") (pinfunction "IO_L67N_M4DQ7_4_H1") (pintype "bidirectional"))
      (node (ref "IC4") (pin "H7") (pinfunction "DQ7_H7") (pintype "bidirectional"))
      (node (ref "R56") (pin "1") (pinfunction "1_1") (pintype "passive"))
    )
    (net (code "35") (name "/DDR_DQ8") (class "Default")
      (node (ref "IC19") (pin "M4") (pinfunction "IO_L63P_M4DQ8_4_M4") (pintype "bidirectional"))
      (node (ref "IC4") (pin "D7") (pinfunction "DQ8_D7") (pintype "bidirectional"))
      (node (ref "R77") (pin "1") (pinfunction "1_1") (pintype "passive"))
    )
    (net (code "36") (name "/DDR_DQ9") (class "Default")
      (node (ref "IC19") (pin "M3") (pinfunction "IO_L63N_M4DQ9_4_M3") (pintype "bidirectional"))
      (node (ref "IC4") (pin "C3") (pinfunction "DQ9_C3") (pintype "bidirectional"))
      (node (ref "R55") (pin "1") (pinfunction "1_1") (pintype "passive"))
    )
    (net (code "37") (name "/DDR_DQ10") (class "Default")
      (node (ref "IC19") (pin "L5") (pinfunction "IO_L62P_M4DQ10_4_L5") (pintype "bidirectional"))
      (node (ref "IC4") (pin "C8") (pinfunction "DQ10_C8") (pintype "bidirectional"))
      (node (ref "R76") (pin "1") (pinfunction "1_1") (pintype "passive"))
    )
    (net (code "38") (name "/DDR_DQ11") (class "Default")
      (node (ref "IC19") (pin "L4") (pinfunction "IO_L62N_M4DQ11_4_L4") (pintype "bidirectional"))
      (node (ref "IC4") (pin "C2") (pinfunction "DQ11_C2") (pintype "bidirectional"))
      (node (ref "R54") (pin "1") (pinfunction "1_1") (pintype "passive"))
    )
    (net (code "39") (name "/DDR_DQ12") (class "Default")
      (node (ref "IC19") (pin "L3") (pinfunction "IO_L60P_M4DQ12_4_L3") (pintype "bidirectional"))
      (node (ref "IC4") (pin "A7") (pinfunction "DQ12_A7") (pintype "bidirectional"))
      (node (ref "R75") (pin "1") (pinfunction "1_1") (pintype "passive"))
    )
    (net (code "40") (name "/DDR_DQ13") (class "Default")
      (node (ref "IC19") (pin "L1") (pinfunction "IO_L60N_M4DQ13_4_L1") (pintype "bidirectional"))
      (node (ref "IC4") (pin "A2") (pinfunction "DQ13_A2") (pintype "bidirectional"))
      (node (ref "R53") (pin "1") (pinfunction "1_1") (pintype "passive"))
    )
    (net (code "41") (name "/DDR_DQ14") (class "Default")
      (node (ref "IC19") (pin "M2") (pinfunction "IO_L59P_M4DQ14_4_M2") (pintype "bidirectional"))
      (node (ref "IC4") (pin "B8") (pinfunction "DQ14_B8") (pintype "bidirectional"))
      (node (ref "R74") (pin "1") (pinfunction "1_1") (pintype "passive"))
    )
    (net (code "42") (name "/DDR_DQ15") (class "Default")
      (node (ref "IC19") (pin "M1") (pinfunction "IO_L59N_M4DQ15_4_M1") (pintype "bidirectional"))
      (node (ref "IC4") (pin "A3") (pinfunction "DQ15_A3") (pintype "bidirectional"))
      (node (ref "R52") (pin "1") (pinfunction "1_1") (pintype "passive"))
    )
    (net (code "44") (name "/DDR_LDM") (class "Default")
      (node (ref "IC19") (pin "K3") (pinfunction "IO_L69N_M4LDM_4_K3") (pintype "bidirectional"))
      (node (ref "IC4") (pin "E7") (pinfunction "LDM_E7") (pintype "input"))
      (node (ref "R94") (pin "1") (pinfunction "1_1") (pintype "passive"))
    )
    (net (code "45") (name "/DDR_LDQS_N") (class "Default")
      (node (ref "IC19") (pin "J4") (pinfunction "IO_L66N_M4LDQSN_4_J4") (pintype "bidirectional"))
      (node (ref "IC4") (pin "G3") (pinfunction "LDQS_G3") (pintype "bidirectional"))
      (node (ref "R49") (pin "1") (pinfunction "1_1") (pintype "passive"))
    )
    (net (code "46") (name "/DDR_LDQS_P") (class "Default")
      (node (ref "IC19") (pin "J5") (pinfunction "IO_L66P_M4LDQS_4_J5") (pintype "bidirectional"))
      (node (ref "IC4") (pin "F3") (pinfunction "LDQS_F3") (pintype "bidirectional"))
      (node (ref "R50") (pin "1") (pinfunction "1_1") (pintype "passive"))
    )
    (net (code "47") (name "/DDR_ODT") (class "Default")
      (node (ref "IC19") (pin "E4") (pinfunction "IO_L72N_M4ODT_4_E4") (pintype "bidirectional"))
      (node (ref "IC4") (pin "K1") (pinfunction "ODT_K1") (pintype "input"))
      (node (ref "R87") (pin "2") (pinfunction "2_2") (pintype "passive"))
    )
    (net (code "48") (name "/DDR_RAS") (class "Default")
      (node (ref "IC19") (pin "C1") (pinfunction "IO_L70P_M4RASN_4_C1") (pintype "bidirectional"))
      (node (ref "IC4") (pin "J3") (pinfunction "RAS_J3") (pintype "input"))
      (node (ref "R63") (pin "1") (pinfunction "1_1") (pintype "passive"))
    )
    (net (code "49") (name "/DDR_RESET") (class "Default")
      (node (ref "IC19") (pin "G5") (pinfunction "IO_L81P_M4RESET_4_G5") (pintype "bidirectional"))
      (node (ref "IC4") (pin "T2") (pinfunction "RESET_T2") (pintype "input"))
      (node (ref "R90") (pin "2") (pinfunction "2_2") (pintype "passive"))
    )
    (net (code "50") (name "/DDR_UDM") (class "Default")
      (node (ref "IC19") (pin "K4") (pinfunction "IO_L69P_M4UDM_4_K4") (pintype "bidirectional"))
      (node (ref "IC4") (pin "D3") (pinfunction "UDM_D3") (pintype "input"))
      (node (ref "R73") (pin "1") (pinfunction "1_1") (pintype "passive"))
    )
    (net (code "51") (name "/DDR_UDQS_N") (class "Default")
      (node (ref "IC19") (pin "K1") (pinfunction "IO_L61N_M4UDQSN_4_K1") (pintype "bidirectional"))
      (node (ref "IC4") (pin "B7") (pinfunction "UDQS_B7") (pintype "bidirectional"))
      (node (ref "R71") (pin "1") (pinfunction "1_1") (pintype "passive"))
    )
    (net (code "52") (name "/DDR_UDQS_P") (class "Default")
      (node (ref "IC19") (pin "K2") (pinfunction "IO_L61P_M4UDQS_4_K2") (pintype "bidirectional"))
      (node (ref "IC4") (pin "C7") (pinfunction "UDQS_C7") (pintype "bidirectional"))
      (node (ref "R72") (pin "1") (pinfunction "1_1") (pintype "passive"))
    )
    (net (code "53") (name "/DDR_WE") (class "Default")
      (node (ref "IC19") (pin "F4") (pinfunction "IO_L77P_M4WE_4_F4") (pintype "bidirectional"))
      (node (ref "IC4") (pin "L3") (pinfunction "WE_L3") (pintype "input"))
      (node (ref "R62") (pin "1") (pinfunction "1_1") (pintype "passive"))
    )
    (net (code "54") (name "/DDR_ZQ") (class "Default")
      (node (ref "IC4") (pin "L8") (pinfunction "ZQ_L8") (pintype "input"))
      (node (ref "R188") (pin "2") (pinfunction "2_2") (pintype "passive"))
    )
    (net (code "55") (name "GND") (class "Default")
      (node (ref "C100") (pin "1") (pinfunction "1_1") (pintype "passive"))
      (node (ref "C101") (pin "1") (pinfunction "1_1") (pintype "passive"))
      (node (ref "C102") (pin "1") (pinfunction "1_1") (pintype "passive"))
      (node (ref "C103") (pin "1") (pinfunction "1_1") (pintype "passive"))
      (node (ref "C104") (pin "1") (pinfunction "1_1") (pintype "passive"))
      (node (ref "C105") (pin "1") (pinfunction "1_1") (pintype "passive"))
      (node (ref "C106") (pin "1") (pinfunction "1_1") (pintype "passive"))
      (node (ref "C107") (pin "1") (pinfunction "1_1") (pintype "passive"))
      (node (ref "C108") (pin "1") (pinfunction "1_1") (pintype "passive"))
      (node (ref "C109") (pin "1") (pinfunction "1_1") (pintype "passive"))
      (node (ref "C110") (pin "1") (pinfunction "1_1") (pintype "passive"))
      (node (ref "C111") (pin "1") (pinfunction "1_1") (pintype "passive"))
      (node (ref "C112") (pin "1") (pinfunction "1_1") (pintype "passive"))
      (node (ref "C113") (pin "1") (pinfunction "1_1") (pintype "passive"))
      (node (ref "C114") (pin "1") (pinfunction "1_1") (pintype "passive"))
      (node (ref "C115") (pin "1") (pinfunction "1_1") (pintype "passive"))
      (node (ref "C116") (pin "1") (pinfunction "1_1") (pintype "passive"))
      (node (ref "C117") (pin "1") (pinfunction "1_1") (pintype "passive"))
      (node (ref "C118") (pin "1") (pinfunction "1_1") (pintype "passive"))
      (node (ref "C152") (pin "1") (pinfunction "1_1") (pintype "passive"))
      (node (ref "C20") (pin "1") (pinfunction "1_1") (pintype "passive"))
      (node (ref "C206") (pin "1") (pinfunction "1_1") (pintype "passive"))
      (node (ref "C235") (pin "1") (pinfunction "1_1") (pintype "passive"))
      (node (ref "C94") (pin "1") (pinfunction "1_1") (pintype "passive"))
      (node (ref "C95") (pin "1") (pinfunction "1_1") (pintype "passive"))
      (node (ref "C96") (pin "1") (pinfunction "1_1") (pintype "passive"))
      (node (ref "C97") (pin "1") (pinfunction "1_1") (pintype "passive"))
      (node (ref "C98") (pin "1") (pinfunction "1_1") (pintype "passive"))
      (node (ref "C99") (pin "1") (pinfunction "1_1") (pintype "passive"))
      (node (ref "IC4") (pin "A9") (pinfunction "VSS_A9") (pintype "power_in"))
      (node (ref "IC4") (pin "B1") (pinfunction "VSSQ_B1") (pintype "power_in"))
      (node (ref "IC4") (pin "B3") (pinfunction "VSS_B3") (pintype "power_in"))
      (node (ref "IC4") (pin "B9") (pinfunction "VSSQ_B9") (pintype "power_in"))
      (node (ref "IC4") (pin "D1") (pinfunction "VSSQ_D1") (pintype "power_in"))
      (node (ref "IC4") (pin "D8") (pinfunction "VSSQ_D8") (pintype "power_in"))
      (node (ref "IC4") (pin "E1") (pinfunction "VSS_E1") (pintype "power_in"))
      (node (ref "IC4") (pin "E2") (pinfunction "VSSQ_E2") (pintype "power_in"))
      (node (ref "IC4") (pin "E8") (pinfunction "VSSQ_E8") (pintype "power_in"))
      (node (ref "IC4") (pin "F9") (pinfunction "VSSQ_F9") (pintype "power_in"))
      (node (ref "IC4") (pin "G1") (pinfunction "VSSQ_G1") (pintype "power_in"))
      (node (ref "IC4") (pin "G8") (pinfunction "VSS_G8") (pintype "power_in"))
      (node (ref "IC4") (pin "G9") (pinfunction "VSSQ_G9") (pintype "power_in"))
      (node (ref "IC4") (pin "J2") (pinfunction "VSS_J2") (pintype "power_in"))
      (node (ref "IC4") (pin "J8") (pinfunction "VSS_J8") (pintype "power_in"))
      (node (ref "IC4") (pin "M1") (pinfunction "VSS_M1") (pintype "power_in"))
      (node (ref "IC4") (pin "M9") (pinfunction "VSS_M9") (pintype "power_in"))
      (node (ref "IC4") (pin "P1") (pinfunction "VSS_P1") (pintype "power_in"))
      (node (ref "IC4") (pin "P9") (pinfunction "VSS_P9") (pintype "power_in"))
      (node (ref "IC4") (pin "T1") (pinfunction "VSS_T1") (pintype "power_in"))
      (node (ref "IC4") (pin "T9") (pinfunction "VSS_T9") (pintype "power_in"))
      (node (ref "R141") (pin "2") (pinfunction "2_2") (pintype "passive"))
      (node (ref "R188") (pin "1") (pinfunction "1_1") (pintype "passive"))
      (node (ref "R87") (pin "1") (pinfunction "1_1") (pintype "passive"))
      (node (ref "R88") (pin "1") (pinfunction "1_1") (pintype "passive"))
      (node (ref "R90") (pin "1") (pinfunction "1_1") (pintype "passive"))
      (node (ref "R91") (pin "2") (pinfunction "2_2") (pintype "passive"))
    )
    (net (code "56") (name "Net-(IC4-NC-PadT7)") (class "Default")
      (node (ref "IC4") (pin "T7") (pinfunction "NC_T7") (pintype "passive"))
      (node (ref "R85") (pin "1") (pinfunction "1_1") (pintype "passive"))
    )
    (net (code "57") (name "Net-(IC19H-IO_L58P_4)") (class "Default")
      (node (ref "IC19") (pin "L7") (pinfunction "IO_L58P_4_L7") (pintype "bidirectional"))
      (node (ref "R91") (pin "1") (pinfunction "1_1") (pintype "passive"))
    )
    (net (code "58") (name "P1V5") (class "Default")
      (node (ref "C103") (pin "2") (pinfunction "2_2") (pintype "passive"))
      (node (ref "C104") (pin "2") (pinfunction "2_2") (pintype "passive"))
      (node (ref "C105") (pin "2") (pinfunction "2_2") (pintype "passive"))
      (node (ref "C106") (pin "2") (pinfunction "2_2") (pintype "passive"))
      (node (ref "C107") (pin "2") (pinfunction "2_2") (pintype "passive"))
      (node (ref "C108") (pin "2") (pinfunction "2_2") (pintype "passive"))
      (node (ref "C109") (pin "2") (pinfunction "2_2") (pintype "passive"))
      (node (ref "C110") (pin "2") (pinfunction "2_2") (pintype "passive"))
      (node (ref "C111") (pin "2") (pinfunction "2_2") (pintype "passive"))
      (node (ref "IC4") (pin "A1") (pinfunction "VDDQ_A1") (pintype "power_in"))
      (node (ref "IC4") (pin "A8") (pinfunction "VDDQ_A8") (pintype "power_in"))
      (node (ref "IC4") (pin "B2") (pinfunction "VDD_B2") (pintype "power_in"))
      (node (ref "IC4") (pin "C1") (pinfunction "VDDQ_C1") (pintype "power_in"))
      (node (ref "IC4") (pin "C9") (pinfunction "VDDQ_C9") (pintype "power_in"))
      (node (ref "IC4") (pin "D2") (pinfunction "VDDQ_D2") (pintype "power_in"))
      (node (ref "IC4") (pin "D9") (pinfunction "VDD_D9") (pintype "power_in"))
      (node (ref "IC4") (pin "E9") (pinfunction "VDDQ_E9") (pintype "power_in"))
      (node (ref "IC4") (pin "F1") (pinfunction "VDDQ_F1") (pintype "power_in"))
      (node (ref "IC4") (pin "G7") (pinfunction "VDD_G7") (pintype "power_in"))
      (node (ref "IC4") (pin "H2") (pinfunction "VDDQ_H2") (pintype "power_in"))
      (node (ref "IC4") (pin "H9") (pinfunction "VDDQ_H9") (pintype "power_in"))
      (node (ref "IC4") (pin "K2") (pinfunction "VDD_K2") (pintype "power_in"))
      (node (ref "IC4") (pin "K8") (pinfunction "VDD_K8") (pintype "power_in"))
      (node (ref "IC4") (pin "N1") (pinfunction "VDD_N1") (pintype "power_in"))
      (node (ref "IC4") (pin "N9") (pinfunction "VDD_N9") (pintype "power_in"))
      (node (ref "IC4") (pin "R1") (pinfunction "VDD_R1") (pintype "power_in"))
      (node (ref "IC4") (pin "R9") (pinfunction "VDD_R9") (pintype "power_in"))
    )
    (net (code "59") (name "VREF_DDR3") (class "Default")
      (node (ref "C152") (pin "2") (pinfunction "2_2") (pintype "passive"))
      (node (ref "C20") (pin "2") (pinfunction "2_2") (pintype "passive"))
      (node (ref "C206") (pin "2") (pinfunction "2_2") (pintype "passive"))
      (node (ref "C235") (pin "2") (pinfunction "2_2") (pintype "passive"))
      (node (ref "C94") (pin "2") (pinfunction "2_2") (pintype "passive"))
      (node (ref "IC19") (pin "H6") (pinfunction "IO_L83N_VREF_4_H6") (pintype "bidirectional"))
      (node (ref "IC19") (pin "L6") (pinfunction "IO_L58N_VREF_4_L6") (pintype "bidirectional"))
      (node (ref "IC4") (pin "H1") (pinfunction "VREFDQ_H1") (pintype "power_in"))
      (node (ref "IC4") (pin "M8") (pinfunction "VREFCA_M8") (pintype "power_in"))
    )
    (net (code "60") (name "VTT_DDR3") (class "Default")
      (node (ref "C100") (pin "2") (pinfunction "2_2") (pintype "passive"))
      (node (ref "C101") (pin "2") (pinfunction "2_2") (pintype "passive"))
      (node (ref "C102") (pin "2") (pinfunction "2_2") (pintype "passive"))
      (node (ref "C112") (pin "2") (pinfunction "2_2") (pintype "passive"))
      (node (ref "C113") (pin "2") (pinfunction "2_2") (pintype "passive"))
      (node (ref "C114") (pin "2") (pinfunction "2_2") (pintype "passive"))
      (node (ref "C115") (pin "2") (pinfunction "2_2") (pintype "passive"))
      (node (ref "C116") (pin "2") (pinfunction "2_2") (pintype "passive"))
      (node (ref "C117") (pin "2") (pinfunction "2_2") (pintype "passive"))
      (node (ref "C118") (pin "2") (pinfunction "2_2") (pintype "passive"))
      (node (ref "C95") (pin "2") (pinfunction "2_2") (pintype "passive"))
      (node (ref "C96") (pin "2") (pinfunction "2_2") (pintype "passive"))
      (node (ref "C97") (pin "2") (pinfunction "2_2") (pintype "passive"))
      (node (ref "C98") (pin "2") (pinfunction "2_2") (pintype "passive"))
      (node (ref "C99") (pin "2") (pinfunction "2_2") (pintype "passive"))
      (node (ref "R39") (pin "2") (pinfunction "2_2") (pintype "passive"))
      (node (ref "R40") (pin "2") (pinfunction "2_2") (pintype "passive"))
      (node (ref "R41") (pin "2") (pinfunction "2_2") (pintype "passive"))
      (node (ref "R42") (pin "2") (pinfunction "2_2") (pintype "passive"))
      (node (ref "R43") (pin "2") (pinfunction "2_2") (pintype "passive"))
      (node (ref "R44") (pin "2") (pinfunction "2_2") (pintype "passive"))
      (node (ref "R45") (pin "2") (pinfunction "2_2") (pintype "passive"))
      (node (ref "R46") (pin "2") (pinfunction "2_2") (pintype "passive"))
      (node (ref "R47") (pin "2") (pinfunction "2_2") (pintype "passive"))
      (node (ref "R48") (pin "2") (pinfunction "2_2") (pintype "passive"))
      (node (ref "R49") (pin "2") (pinfunction "2_2") (pintype "passive"))
      (node (ref "R50") (pin "2") (pinfunction "2_2") (pintype "passive"))
      (node (ref "R52") (pin "2") (pinfunction "2_2") (pintype "passive"))
      (node (ref "R53") (pin "2") (pinfunction "2_2") (pintype "passive"))
      (node (ref "R54") (pin "2") (pinfunction "2_2") (pintype "passive"))
      (node (ref "R55") (pin "2") (pinfunction "2_2") (pintype "passive"))
      (node (ref "R56") (pin "2") (pinfunction "2_2") (pintype "passive"))
      (node (ref "R57") (pin "2") (pinfunction "2_2") (pintype "passive"))
      (node (ref "R58") (pin "2") (pinfunction "2_2") (pintype "passive"))
      (node (ref "R59") (pin "2") (pinfunction "2_2") (pintype "passive"))
      (node (ref "R61") (pin "2") (pinfunction "2_2") (pintype "passive"))
      (node (ref "R62") (pin "2") (pinfunction "2_2") (pintype "passive"))
      (node (ref "R63") (pin "2") (pinfunction "2_2") (pintype "passive"))
      (node (ref "R64") (pin "2") (pinfunction "2_2") (pintype "passive"))
      (node (ref "R65") (pin "2") (pinfunction "2_2") (pintype "passive"))
      (node (ref "R66") (pin "2") (pinfunction "2_2") (pintype "passive"))
      (node (ref "R67") (pin "2") (pinfunction "2_2") (pintype "passive"))
      (node (ref "R68") (pin "2") (pinfunction "2_2") (pintype "passive"))
      (node (ref "R69") (pin "2") (pinfunction "2_2") (pintype "passive"))
      (node (ref "R70") (pin "2") (pinfunction "2_2") (pintype "passive"))
      (node (ref "R71") (pin "2") (pinfunction "2_2") (pintype "passive"))
      (node (ref "R72") (pin "2") (pinfunction "2_2") (pintype "passive"))
      (node (ref "R73") (pin "2") (pinfunction "2_2") (pintype "passive"))
      (node (ref "R74") (pin "2") (pinfunction "2_2") (pintype "passive"))
      (node (ref "R75") (pin "2") (pinfunction "2_2") (pintype "passive"))
      (node (ref "R76") (pin "2") (pinfunction "2_2") (pintype "passive"))
      (node (ref "R77") (pin "2") (pinfunction "2_2") (pintype "passive"))
      (node (ref "R78") (pin "2") (pinfunction "2_2") (pintype "passive"))
      (node (ref "R79") (pin "2") (pinfunction "2_2") (pintype "passive"))
      (node (ref "R80") (pin "2") (pinfunction "2_2") (pintype "passive"))
      (node (ref "R81") (pin "2") (pinfunction "2_2") (pintype "passive"))
      (node (ref "R85") (pin "2") (pinfunction "2_2") (pintype "passive"))
      (node (ref "R94") (pin "2") (pinfunction "2_2") (pintype "passive"))
    )
    (net (code "61") (name "unconnected-(IC4-NC-PadJ1)") (class "Default")
      (node (ref "IC4") (pin "J1") (pinfunction "NC_J1") (pintype "passive+no_connect"))
    )
    (net (code "62") (name "unconnected-(IC4-NC-PadJ9)") (class "Default")
      (node (ref "IC4") (pin "J9") (pinfunction "NC_J9") (pintype "passive+no_connect"))
    )
    (net (code "63") (name "unconnected-(IC4-NC-PadL1)") (class "Default")
      (node (ref "IC4") (pin "L1") (pinfunction "NC_L1") (pintype "passive+no_connect"))
    )
    (net (code "64") (name "unconnected-(IC4-NC-PadL9)") (class "Default")
      (node (ref "IC4") (pin "L9") (pinfunction "NC_L9") (pintype "passive+no_connect"))
    )
    (net (code "65") (name "unconnected-(IC4-NC-PadM7)") (class "Default")
      (node (ref "IC4") (pin "M7") (pinfunction "NC_M7") (pintype "passive+no_connect"))
    )
    (net (code "66") (name "unconnected-(IC19H-IO_L83P_4-PadJ6)") (class "Default")
      (node (ref "IC19") (pin "J6") (pinfunction "IO_L83P_4_J6") (pintype "bidirectional"))
    )
  )
)
